# Senaino.net
KiCad netlist of a schematic drawn in EAGLE
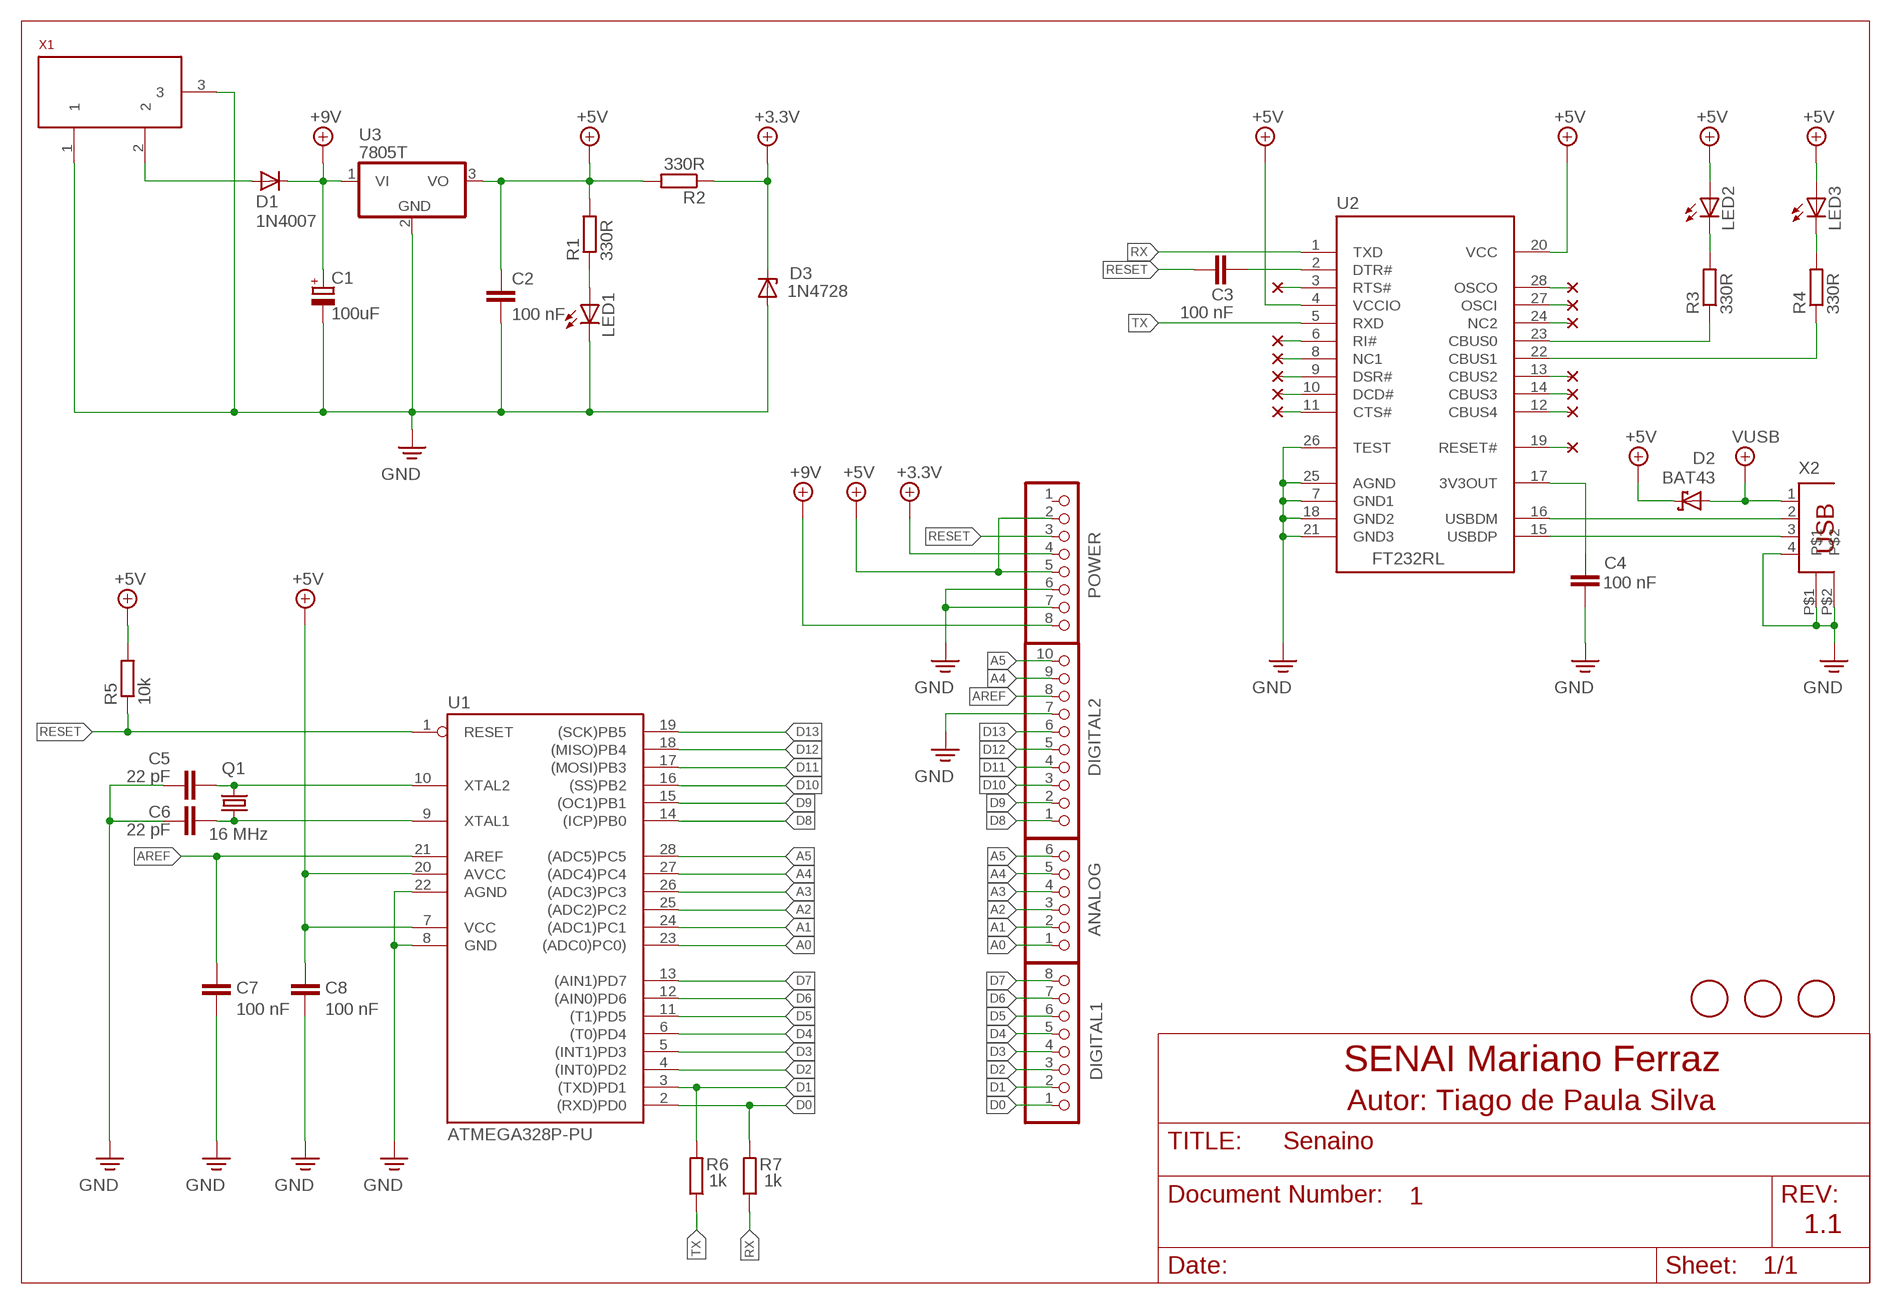
[diagram p0: schematic, sheet 1]

(export (version "E")
  (design (tool "Eeschema 10.0.6"))
  (components
    (comp (ref "ANALOG")
      (value "PINHD-1X6")
      (footprint "eagle-import:1X06")
      (libsource (lib "eagle-import") (part "PINHD-1X6"))
    )
    (comp (ref "C1")
      (value "100uF")
      (footprint "eagle-import:E2-5")
      (libsource (lib "eagle-import") (part "CPOL-EUE2-5"))
    )
    (comp (ref "C2")
      (value "100 nF")
      (footprint "eagle-import:C025-024X044")
      (libsource (lib "eagle-import") (part "C-EU025-024X044"))
    )
    (comp (ref "C3")
      (value "100 nF")
      (footprint "eagle-import:C025-024X044")
      (libsource (lib "eagle-import") (part "C-EU025-024X044"))
    )
    (comp (ref "C4")
      (value "100 nF")
      (footprint "eagle-import:C025-024X044")
      (libsource (lib "eagle-import") (part "C-EU025-024X044"))
    )
    (comp (ref "C5")
      (value "22 pF")
      (footprint "eagle-import:C025-024X044")
      (libsource (lib "eagle-import") (part "C-EU025-024X044"))
    )
    (comp (ref "C6")
      (value "22 pF")
      (footprint "eagle-import:C025-024X044")
      (libsource (lib "eagle-import") (part "C-EU025-024X044"))
    )
    (comp (ref "C7")
      (value "100 nF")
      (footprint "eagle-import:C025-024X044")
      (libsource (lib "eagle-import") (part "C-EU025-024X044"))
    )
    (comp (ref "C8")
      (value "100 nF")
      (footprint "eagle-import:C025-024X044")
      (libsource (lib "eagle-import") (part "C-EU025-024X044"))
    )
    (comp (ref "D1")
      (value "1N4007")
      (footprint "eagle-import:DO35-7")
      (libsource (lib "eagle-import") (part "1N4148DO35-7"))
    )
    (comp (ref "D2")
      (value "BAT43")
      (footprint "eagle-import:DIODE_DO35-7")
      (libsource (lib "eagle-import") (part "SCHOTTKY-DIODEDO35-7"))
    )
    (comp (ref "D3")
      (value "1N4728")
      (footprint "eagle-import:DO41Z10")
      (libsource (lib "eagle-import") (part "1N4728"))
    )
    (comp (ref "DIGITAL1")
      (value "PINHD-1X8")
      (footprint "eagle-import:1X08")
      (libsource (lib "eagle-import") (part "PINHD-1X8"))
    )
    (comp (ref "DIGITAL2")
      (value "PINHD-1X10_ARD")
      (footprint "eagle-import:1X10")
      (libsource (lib "eagle-import") (part "PINHD-1X10_ARD"))
    )
    (comp (ref "FD1")
      (value "FIDUCIALMOUNT")
      (footprint "eagle-import:FIDUCIA-MOUNT")
      (libsource (lib "eagle-import") (part "FIDUCIALMOUNT"))
    )
    (comp (ref "FD2")
      (value "FIDUCIALMOUNT")
      (footprint "eagle-import:FIDUCIA-MOUNT")
      (libsource (lib "eagle-import") (part "FIDUCIALMOUNT"))
    )
    (comp (ref "FD3")
      (value "FIDUCIALMOUNT")
      (footprint "eagle-import:FIDUCIA-MOUNT")
      (libsource (lib "eagle-import") (part "FIDUCIALMOUNT"))
    )
    (comp (ref "LED1")
      (value "LED3MM")
      (footprint "eagle-import:LED3MM")
      (libsource (lib "eagle-import") (part "LED3MM"))
    )
    (comp (ref "LED2")
      (value "LED3MM")
      (footprint "eagle-import:LED3MM")
      (libsource (lib "eagle-import") (part "LED3MM"))
    )
    (comp (ref "LED3")
      (value "LED3MM")
      (footprint "eagle-import:LED3MM")
      (libsource (lib "eagle-import") (part "LED3MM"))
    )
    (comp (ref "POWER")
      (value "PINHD-1X8")
      (footprint "eagle-import:1X08")
      (libsource (lib "eagle-import") (part "PINHD-1X8"))
    )
    (comp (ref "Q1")
      (value "16 MHz")
      (footprint "eagle-import:HC49_S")
      (libsource (lib "eagle-import") (part "CRYSTALHC49S"))
    )
    (comp (ref "R1")
      (value "330R")
      (footprint "eagle-import:0204_7")
      (libsource (lib "eagle-import") (part "R-EU_0204/7"))
    )
    (comp (ref "R2")
      (value "330R")
      (footprint "eagle-import:0204_7")
      (libsource (lib "eagle-import") (part "R-EU_0204/7"))
    )
    (comp (ref "R3")
      (value "330R")
      (footprint "eagle-import:0204_7")
      (libsource (lib "eagle-import") (part "R-EU_0204/7"))
    )
    (comp (ref "R4")
      (value "330R")
      (footprint "eagle-import:0204_7")
      (libsource (lib "eagle-import") (part "R-EU_0204/7"))
    )
    (comp (ref "R5")
      (value "10k")
      (footprint "eagle-import:0204_7")
      (libsource (lib "eagle-import") (part "R-EU_0204/7"))
    )
    (comp (ref "R6")
      (value "1k")
      (footprint "eagle-import:0204_7")
      (libsource (lib "eagle-import") (part "R-EU_0204/7"))
    )
    (comp (ref "R7")
      (value "1k")
      (footprint "eagle-import:0204_7")
      (libsource (lib "eagle-import") (part "R-EU_0204/7"))
    )
    (comp (ref "U1")
      (value "ATMEGA328P-PU")
      (footprint "eagle-import:DIL28-3")
      (libsource (lib "eagle-import") (part "ATMEGA328P-PU"))
    )
    (comp (ref "U2")
      (value "FT232RL")
      (footprint "eagle-import:SSOP28")
      (libsource (lib "eagle-import") (part "FT232RL"))
    )
    (comp (ref "U3")
      (value "7805T")
      (footprint "eagle-import:TO220H")
      (libsource (lib "eagle-import") (part "78T05"))
    )
    (comp (ref "X1")
      (value "POWERSUPPLY_DC21MMX")
      (footprint "eagle-import:POWERSUPPLY_DC-21MM")
      (libsource (lib "eagle-import") (part "POWERSUPPLY_DC21MMX"))
    )
    (comp (ref "X2")
      (value "PN61729")
      (footprint "eagle-import:PN61729")
      (libsource (lib "eagle-import") (part "PN61729"))
    )
  )
  (nets
    (net (code "1") (name "+3.3V") (class "Default")
      (node (ref "D3") (pin "C") (pinfunction "C_C") (pintype "passive"))
      (node (ref "POWER") (pin "4") (pinfunction "4_4") (pintype "passive"))
      (node (ref "R2") (pin "1") (pinfunction "1_1") (pintype "passive"))
    )
    (net (code "2") (name "+5V") (class "Default")
      (node (ref "C2") (pin "1") (pinfunction "1_1") (pintype "passive"))
      (node (ref "C8") (pin "1") (pinfunction "1_1") (pintype "passive"))
      (node (ref "D2") (pin "C") (pinfunction "A_C") (pintype "passive"))
      (node (ref "LED2") (pin "A") (pinfunction "A_A") (pintype "passive"))
      (node (ref "LED3") (pin "A") (pinfunction "A_A") (pintype "passive"))
      (node (ref "POWER") (pin "2") (pinfunction "2_2") (pintype "passive"))
      (node (ref "POWER") (pin "5") (pinfunction "5_5") (pintype "passive"))
      (node (ref "R1") (pin "2") (pinfunction "2_2") (pintype "passive"))
      (node (ref "R2") (pin "2") (pinfunction "2_2") (pintype "passive"))
      (node (ref "R5") (pin "2") (pinfunction "2_2") (pintype "passive"))
      (node (ref "U1") (pin "20") (pinfunction "AVCC_20") (pintype "power_in"))
      (node (ref "U1") (pin "7") (pinfunction "VCC_7") (pintype "power_in"))
      (node (ref "U2") (pin "20") (pinfunction "VCC_20") (pintype "power_in"))
      (node (ref "U2") (pin "4") (pinfunction "VCCIO_4") (pintype "power_in"))
      (node (ref "U3") (pin "3") (pinfunction "VO_3") (pintype "passive"))
    )
    (net (code "3") (name "+9V") (class "Default")
      (node (ref "C1") (pin "+") (pinfunction "+_+") (pintype "passive"))
      (node (ref "D1") (pin "C") (pinfunction "C_C") (pintype "passive"))
      (node (ref "POWER") (pin "8") (pinfunction "8_8") (pintype "passive"))
      (node (ref "U3") (pin "1") (pinfunction "VI_1") (pintype "input"))
    )
    (net (code "4") (name "A0") (class "Default")
      (node (ref "ANALOG") (pin "1") (pinfunction "1_1") (pintype "passive"))
      (node (ref "U1") (pin "23") (pinfunction "(ADC0)PC0)_23") (pintype "bidirectional"))
    )
    (net (code "5") (name "A1") (class "Default")
      (node (ref "ANALOG") (pin "2") (pinfunction "2_2") (pintype "passive"))
      (node (ref "U1") (pin "24") (pinfunction "(ADC1)PC1_24") (pintype "bidirectional"))
    )
    (net (code "6") (name "A2") (class "Default")
      (node (ref "ANALOG") (pin "3") (pinfunction "3_3") (pintype "passive"))
      (node (ref "U1") (pin "25") (pinfunction "(ADC2)PC2_25") (pintype "bidirectional"))
    )
    (net (code "7") (name "A3") (class "Default")
      (node (ref "ANALOG") (pin "4") (pinfunction "4_4") (pintype "passive"))
      (node (ref "U1") (pin "26") (pinfunction "(ADC3)PC3_26") (pintype "bidirectional"))
    )
    (net (code "8") (name "A4") (class "Default")
      (node (ref "ANALOG") (pin "5") (pinfunction "5_5") (pintype "passive"))
      (node (ref "DIGITAL2") (pin "9") (pinfunction "9_9") (pintype "passive"))
      (node (ref "U1") (pin "27") (pinfunction "(ADC4)PC4_27") (pintype "bidirectional"))
    )
    (net (code "9") (name "A5") (class "Default")
      (node (ref "ANALOG") (pin "6") (pinfunction "6_6") (pintype "passive"))
      (node (ref "DIGITAL2") (pin "10") (pinfunction "10_10") (pintype "passive"))
      (node (ref "U1") (pin "28") (pinfunction "(ADC5)PC5_28") (pintype "bidirectional"))
    )
    (net (code "10") (name "AREF") (class "Default")
      (node (ref "C7") (pin "1") (pinfunction "1_1") (pintype "passive"))
      (node (ref "DIGITAL2") (pin "8") (pinfunction "8_8") (pintype "passive"))
      (node (ref "U1") (pin "21") (pinfunction "AREF_21") (pintype "passive"))
    )
    (net (code "11") (name "D0") (class "Default")
      (node (ref "DIGITAL1") (pin "1") (pinfunction "1_1") (pintype "passive"))
      (node (ref "R7") (pin "2") (pinfunction "2_2") (pintype "passive"))
      (node (ref "U1") (pin "2") (pinfunction "(RXD)PD0_2") (pintype "bidirectional"))
    )
    (net (code "12") (name "D1") (class "Default")
      (node (ref "DIGITAL1") (pin "2") (pinfunction "2_2") (pintype "passive"))
      (node (ref "R6") (pin "2") (pinfunction "2_2") (pintype "passive"))
      (node (ref "U1") (pin "3") (pinfunction "(TXD)PD1_3") (pintype "bidirectional"))
    )
    (net (code "13") (name "D2") (class "Default")
      (node (ref "DIGITAL1") (pin "3") (pinfunction "3_3") (pintype "passive"))
      (node (ref "U1") (pin "4") (pinfunction "(INT0)PD2_4") (pintype "bidirectional"))
    )
    (net (code "14") (name "D3") (class "Default")
      (node (ref "DIGITAL1") (pin "4") (pinfunction "4_4") (pintype "passive"))
      (node (ref "U1") (pin "5") (pinfunction "(INT1)PD3_5") (pintype "bidirectional"))
    )
    (net (code "15") (name "D4") (class "Default")
      (node (ref "DIGITAL1") (pin "5") (pinfunction "5_5") (pintype "passive"))
      (node (ref "U1") (pin "6") (pinfunction "(T0)PD4_6") (pintype "bidirectional"))
    )
    (net (code "16") (name "D5") (class "Default")
      (node (ref "DIGITAL1") (pin "6") (pinfunction "6_6") (pintype "passive"))
      (node (ref "U1") (pin "11") (pinfunction "(T1)PD5_11") (pintype "bidirectional"))
    )
    (net (code "17") (name "D6") (class "Default")
      (node (ref "DIGITAL1") (pin "7") (pinfunction "7_7") (pintype "passive"))
      (node (ref "U1") (pin "12") (pinfunction "(AIN0)PD6_12") (pintype "bidirectional"))
    )
    (net (code "18") (name "D7") (class "Default")
      (node (ref "DIGITAL1") (pin "8") (pinfunction "8_8") (pintype "passive"))
      (node (ref "U1") (pin "13") (pinfunction "(AIN1)PD7_13") (pintype "bidirectional"))
    )
    (net (code "19") (name "D8") (class "Default")
      (node (ref "DIGITAL2") (pin "1") (pinfunction "1_1") (pintype "passive"))
      (node (ref "U1") (pin "14") (pinfunction "(ICP)PB0_14") (pintype "bidirectional"))
    )
    (net (code "20") (name "D9") (class "Default")
      (node (ref "DIGITAL2") (pin "2") (pinfunction "2_2") (pintype "passive"))
      (node (ref "U1") (pin "15") (pinfunction "(OC1)PB1_15") (pintype "bidirectional"))
    )
    (net (code "21") (name "D10") (class "Default")
      (node (ref "DIGITAL2") (pin "3") (pinfunction "3_3") (pintype "passive"))
      (node (ref "U1") (pin "16") (pinfunction "(SS)PB2_16") (pintype "bidirectional"))
    )
    (net (code "22") (name "D11") (class "Default")
      (node (ref "DIGITAL2") (pin "4") (pinfunction "4_4") (pintype "passive"))
      (node (ref "U1") (pin "17") (pinfunction "(MOSI)PB3_17") (pintype "bidirectional"))
    )
    (net (code "23") (name "D12") (class "Default")
      (node (ref "DIGITAL2") (pin "5") (pinfunction "5_5") (pintype "passive"))
      (node (ref "U1") (pin "18") (pinfunction "(MISO)PB4_18") (pintype "bidirectional"))
    )
    (net (code "24") (name "D13") (class "Default")
      (node (ref "DIGITAL2") (pin "6") (pinfunction "6_6") (pintype "passive"))
      (node (ref "U1") (pin "19") (pinfunction "(SCK)PB5_19") (pintype "bidirectional"))
    )
    (net (code "25") (name "GND") (class "Default")
      (node (ref "C1") (pin "-") (pinfunction "-_-") (pintype "passive"))
      (node (ref "C2") (pin "2") (pinfunction "2_2") (pintype "passive"))
      (node (ref "C4") (pin "1") (pinfunction "1_1") (pintype "passive"))
      (node (ref "C5") (pin "1") (pinfunction "1_1") (pintype "passive"))
      (node (ref "C6") (pin "1") (pinfunction "1_1") (pintype "passive"))
      (node (ref "C7") (pin "2") (pinfunction "2_2") (pintype "passive"))
      (node (ref "C8") (pin "2") (pinfunction "2_2") (pintype "passive"))
      (node (ref "D3") (pin "A") (pinfunction "A_A") (pintype "passive"))
      (node (ref "DIGITAL2") (pin "7") (pinfunction "7_7") (pintype "passive"))
      (node (ref "LED1") (pin "K") (pinfunction "C_K") (pintype "passive"))
      (node (ref "POWER") (pin "6") (pinfunction "6_6") (pintype "passive"))
      (node (ref "POWER") (pin "7") (pinfunction "7_7") (pintype "passive"))
      (node (ref "U1") (pin "22") (pinfunction "AGND_22") (pintype "power_in"))
      (node (ref "U1") (pin "8") (pinfunction "GND_8") (pintype "power_in"))
      (node (ref "U2") (pin "18") (pinfunction "GND2_18") (pintype "power_in"))
      (node (ref "U2") (pin "21") (pinfunction "GND3_21") (pintype "power_in"))
      (node (ref "U2") (pin "25") (pinfunction "AGND_25") (pintype "power_in"))
      (node (ref "U2") (pin "26") (pinfunction "TEST_26") (pintype "input"))
      (node (ref "U2") (pin "7") (pinfunction "GND1_7") (pintype "power_in"))
      (node (ref "U3") (pin "2") (pinfunction "GND_2") (pintype "passive"))
      (node (ref "X1") (pin "1") (pinfunction "1_1") (pintype "power_in"))
      (node (ref "X1") (pin "3") (pinfunction "3_3") (pintype "power_in"))
      (node (ref "X2") (pin "4") (pinfunction "4_4") (pintype "bidirectional"))
      (node (ref "X2") (pin "P$1") (pinfunction "P$1_P$1") (pintype "bidirectional"))
      (node (ref "X2") (pin "P$2") (pinfunction "P$2_P$2") (pintype "bidirectional"))
    )
    (net (code "26") (name "Net-(D1-PadA)") (class "Default")
      (node (ref "D1") (pin "A") (pinfunction "A_A") (pintype "passive"))
      (node (ref "X1") (pin "2") (pinfunction "2_2") (pintype "power_in"))
    )
    (net (code "27") (name "Net-(LED1-PadA)") (class "Default")
      (node (ref "LED1") (pin "A") (pinfunction "A_A") (pintype "passive"))
      (node (ref "R1") (pin "1") (pinfunction "1_1") (pintype "passive"))
    )
    (net (code "28") (name "Net-(LED2-C)") (class "Default")
      (node (ref "LED2") (pin "K") (pinfunction "C_K") (pintype "passive"))
      (node (ref "R3") (pin "2") (pinfunction "2_2") (pintype "passive"))
    )
    (net (code "29") (name "Net-(LED3-C)") (class "Default")
      (node (ref "LED3") (pin "K") (pinfunction "C_K") (pintype "passive"))
      (node (ref "R4") (pin "2") (pinfunction "2_2") (pintype "passive"))
    )
    (net (code "30") (name "Net-(U1-XTAL1)") (class "Default")
      (node (ref "C6") (pin "2") (pinfunction "2_2") (pintype "passive"))
      (node (ref "Q1") (pin "1") (pinfunction "1_1") (pintype "passive"))
      (node (ref "U1") (pin "9") (pinfunction "XTAL1_9") (pintype "bidirectional"))
    )
    (net (code "31") (name "Net-(U1-XTAL2)") (class "Default")
      (node (ref "C5") (pin "2") (pinfunction "2_2") (pintype "passive"))
      (node (ref "Q1") (pin "2") (pinfunction "2_2") (pintype "passive"))
      (node (ref "U1") (pin "10") (pinfunction "XTAL2_10") (pintype "bidirectional"))
    )
    (net (code "32") (name "Net-(U2-3V3OUT)") (class "Default")
      (node (ref "C4") (pin "2") (pinfunction "2_2") (pintype "passive"))
      (node (ref "U2") (pin "17") (pinfunction "3V3OUT_17") (pintype "power_in"))
    )
    (net (code "33") (name "Net-(U2-CBUS0)") (class "Default")
      (node (ref "R3") (pin "1") (pinfunction "1_1") (pintype "passive"))
      (node (ref "U2") (pin "23") (pinfunction "CBUS0_23") (pintype "bidirectional"))
    )
    (net (code "34") (name "Net-(U2-CBUS1)") (class "Default")
      (node (ref "R4") (pin "1") (pinfunction "1_1") (pintype "passive"))
      (node (ref "U2") (pin "22") (pinfunction "CBUS1_22") (pintype "bidirectional"))
    )
    (net (code "35") (name "Net-(U2-DTR#)") (class "Default")
      (node (ref "C3") (pin "2") (pinfunction "2_2") (pintype "passive"))
      (node (ref "U2") (pin "2") (pinfunction "DTR#_2") (pintype "output"))
    )
    (net (code "36") (name "Net-(U2-USBDM)") (class "Default")
      (node (ref "U2") (pin "16") (pinfunction "USBDM_16") (pintype "bidirectional"))
      (node (ref "X2") (pin "2") (pinfunction "2_2") (pintype "bidirectional"))
    )
    (net (code "37") (name "Net-(U2-USBDP)") (class "Default")
      (node (ref "U2") (pin "15") (pinfunction "USBDP_15") (pintype "bidirectional"))
      (node (ref "X2") (pin "3") (pinfunction "3_3") (pintype "bidirectional"))
    )
    (net (code "38") (name "RESET") (class "Default")
      (node (ref "C3") (pin "1") (pinfunction "1_1") (pintype "passive"))
      (node (ref "POWER") (pin "3") (pinfunction "3_3") (pintype "passive"))
      (node (ref "R5") (pin "1") (pinfunction "1_1") (pintype "passive"))
      (node (ref "U1") (pin "1") (pinfunction "RESET_1") (pintype "input"))
    )
    (net (code "39") (name "RX") (class "Default")
      (node (ref "R7") (pin "1") (pinfunction "1_1") (pintype "passive"))
      (node (ref "U2") (pin "1") (pinfunction "TXD_1") (pintype "output"))
    )
    (net (code "40") (name "TX") (class "Default")
      (node (ref "R6") (pin "1") (pinfunction "1_1") (pintype "passive"))
      (node (ref "U2") (pin "5") (pinfunction "RXD_5") (pintype "input"))
    )
    (net (code "41") (name "VUSB") (class "Default")
      (node (ref "D2") (pin "A") (pinfunction "C_A") (pintype "passive"))
      (node (ref "X2") (pin "1") (pinfunction "1_1") (pintype "bidirectional"))
    )
    (net (code "42") (name "unconnected-(POWER-Pad1)") (class "Default")
      (node (ref "POWER") (pin "1") (pinfunction "1_1") (pintype "passive"))
    )
    (net (code "43") (name "unconnected-(U2-CBUS2-Pad13)") (class "Default")
      (node (ref "U2") (pin "13") (pinfunction "CBUS2_13") (pintype "bidirectional"))
    )
    (net (code "44") (name "unconnected-(U2-CBUS3-Pad14)") (class "Default")
      (node (ref "U2") (pin "14") (pinfunction "CBUS3_14") (pintype "bidirectional"))
    )
    (net (code "45") (name "unconnected-(U2-CBUS4-Pad12)") (class "Default")
      (node (ref "U2") (pin "12") (pinfunction "CBUS4_12") (pintype "bidirectional"))
    )
    (net (code "46") (name "unconnected-(U2-CTS#-Pad11)") (class "Default")
      (node (ref "U2") (pin "11") (pinfunction "CTS#_11") (pintype "input"))
    )
    (net (code "47") (name "unconnected-(U2-DCD#-Pad10)") (class "Default")
      (node (ref "U2") (pin "10") (pinfunction "DCD#_10") (pintype "input"))
    )
    (net (code "48") (name "unconnected-(U2-DSR#-Pad9)") (class "Default")
      (node (ref "U2") (pin "9") (pinfunction "DSR#_9") (pintype "input"))
    )
    (net (code "49") (name "unconnected-(U2-NC1-Pad8)") (class "Default")
      (node (ref "U2") (pin "8") (pinfunction "NC1_8") (pintype "no_connect"))
    )
    (net (code "50") (name "unconnected-(U2-NC2-Pad24)") (class "Default")
      (node (ref "U2") (pin "24") (pinfunction "NC2_24") (pintype "no_connect"))
    )
    (net (code "51") (name "unconnected-(U2-OSCI-Pad27)") (class "Default")
      (node (ref "U2") (pin "27") (pinfunction "OSCI_27") (pintype "input"))
    )
    (net (code "52") (name "unconnected-(U2-OSCO-Pad28)") (class "Default")
      (node (ref "U2") (pin "28") (pinfunction "OSCO_28") (pintype "output"))
    )
    (net (code "53") (name "unconnected-(U2-RESET#-Pad19)") (class "Default")
      (node (ref "U2") (pin "19") (pinfunction "RESET#_19") (pintype "input"))
    )
    (net (code "54") (name "unconnected-(U2-RI#-Pad6)") (class "Default")
      (node (ref "U2") (pin "6") (pinfunction "RI#_6") (pintype "input"))
    )
    (net (code "55") (name "unconnected-(U2-RTS#-Pad3)") (class "Default")
      (node (ref "U2") (pin "3") (pinfunction "RTS#_3") (pintype "output"))
    )
  )
)
